# SCH_USB-HUB_2024-07-15.net
KiCad netlist of a schematic drawn in EasyEDA
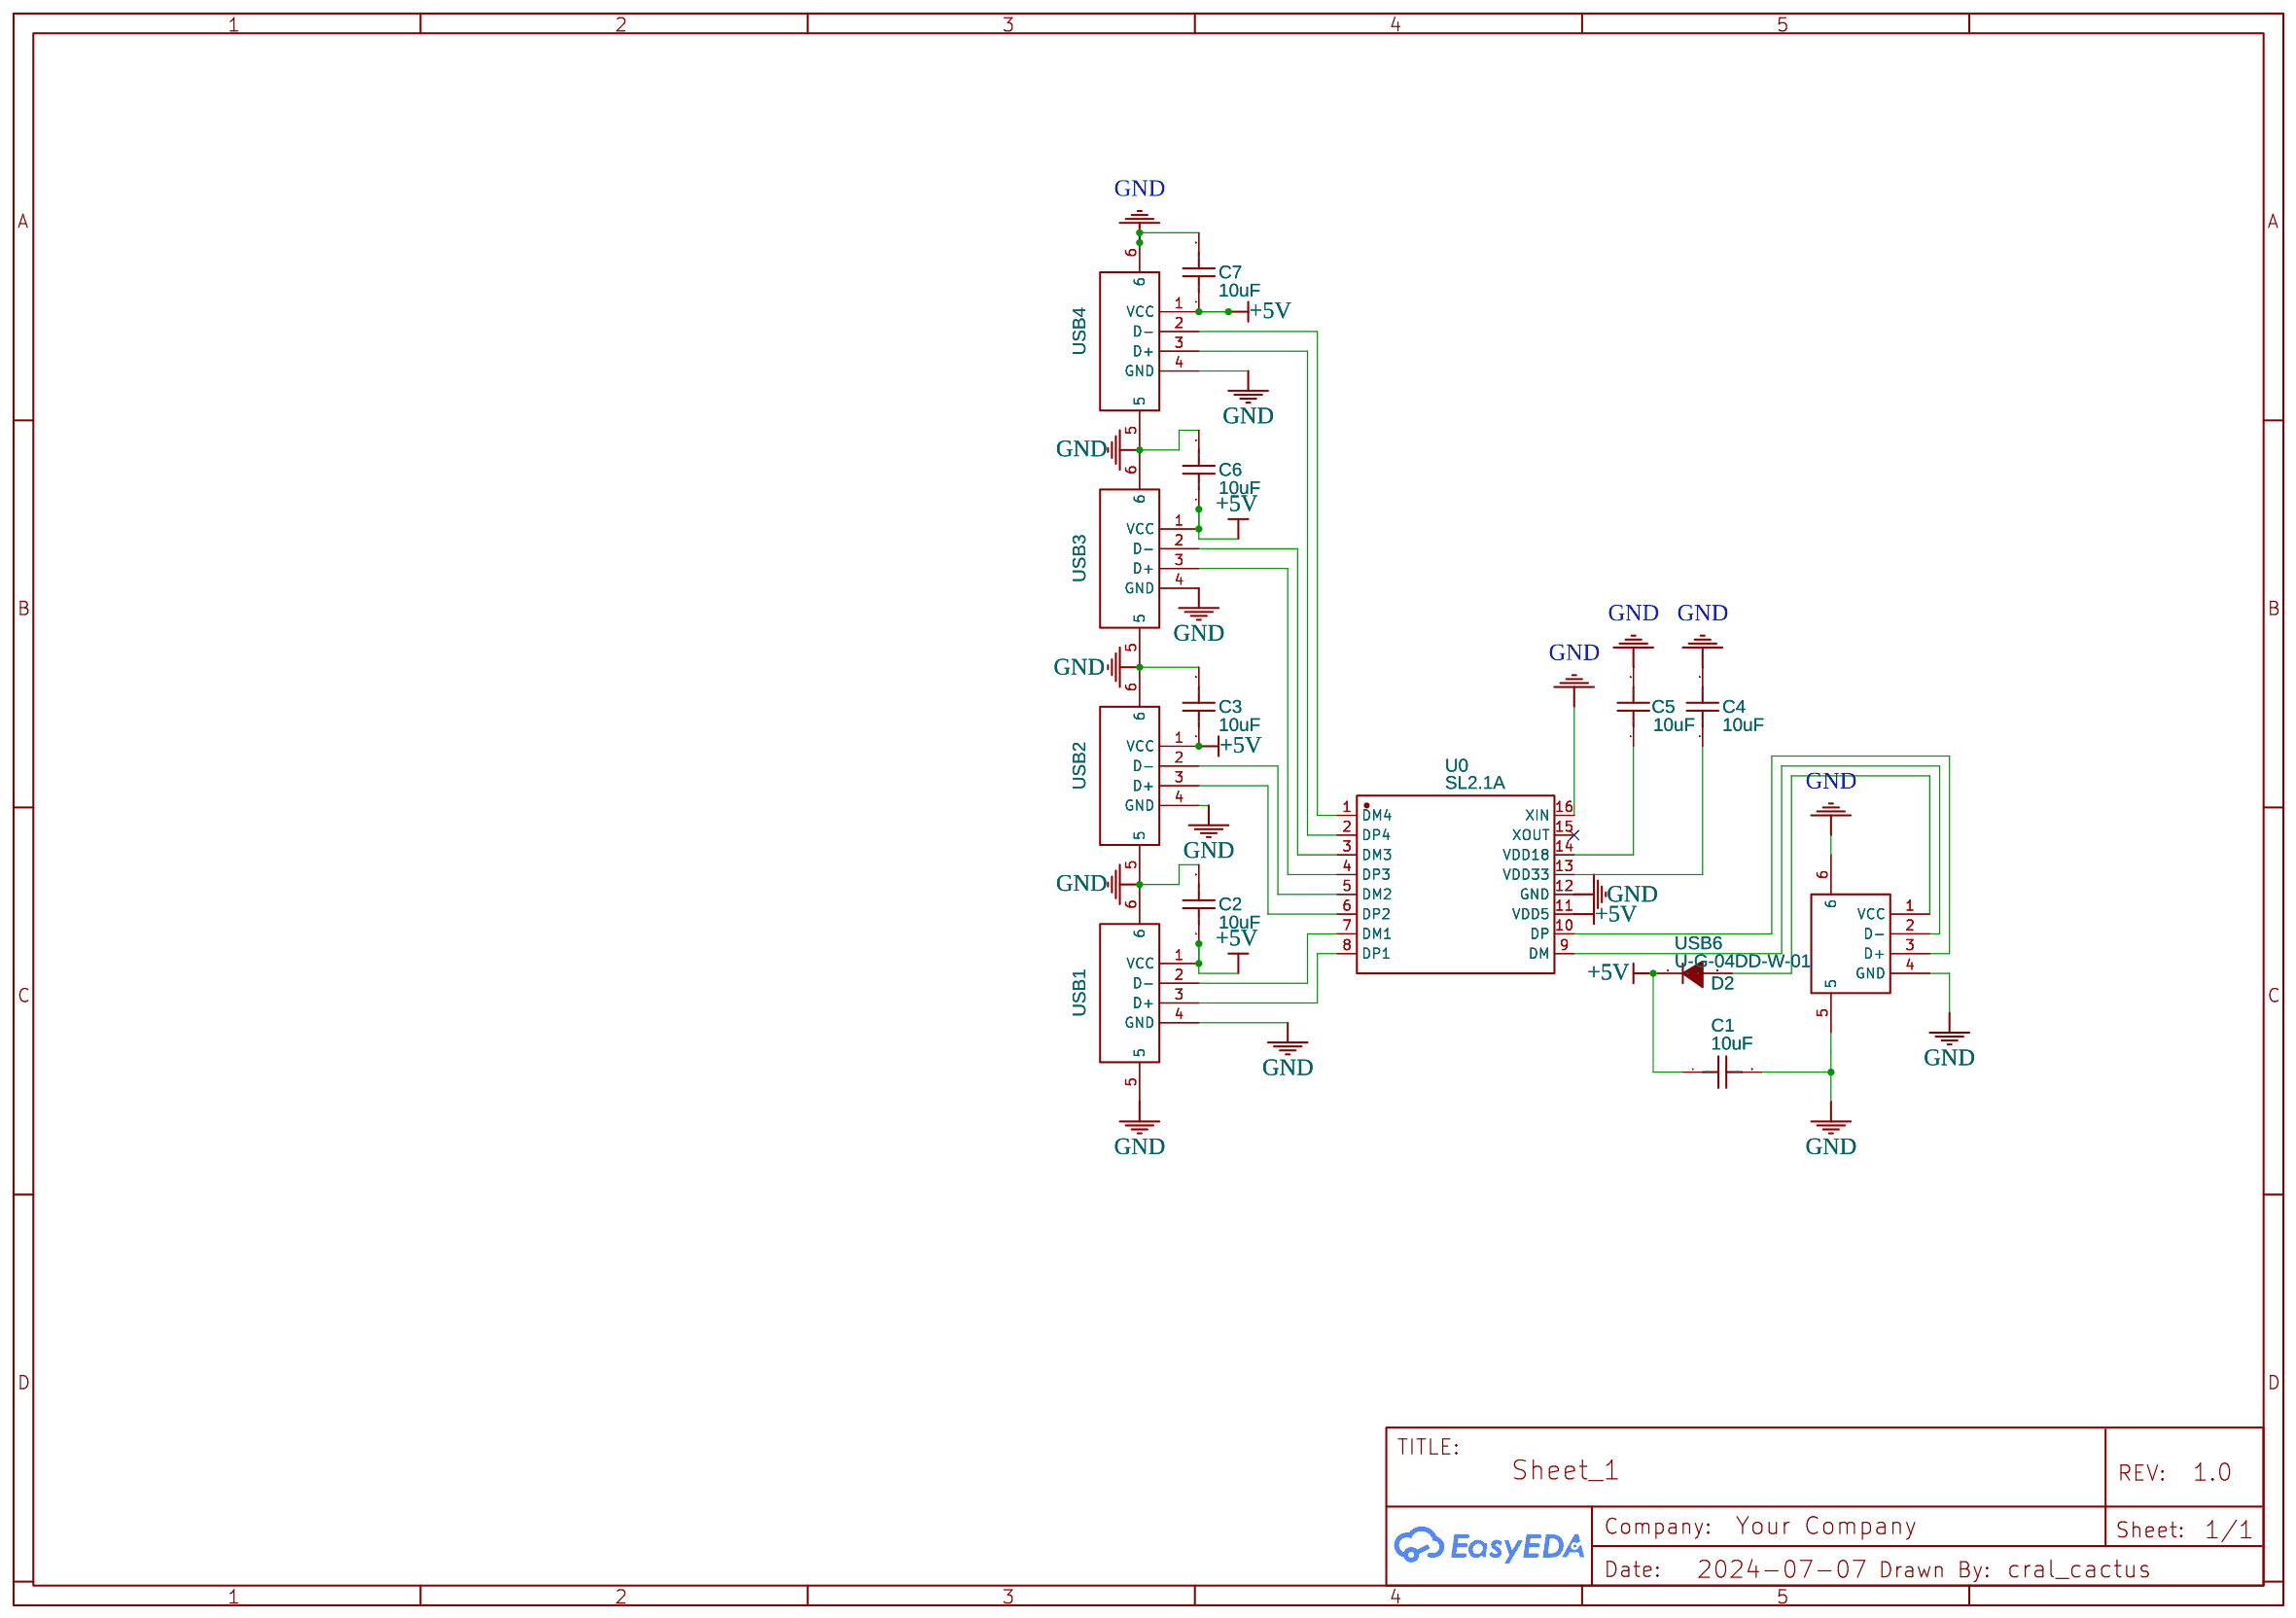
[diagram p0: schematic sheet]

(export (version "E")
  (design (tool "Eeschema 10.0.6"))
  (components
    (comp (ref "C1")
      (value "10uF")
      (fields
        (field (name "Manufacturer Part") "CL10A106KP8NNNC")
        (field (name "Manufacturer") "SAMSUNG(三星)")
      )
      (libsource (lib "") (part "CL10A106KP8NNNC_1"))
    )
    (comp (ref "C2")
      (value "10uF")
      (fields
        (field (name "Manufacturer Part") "CL10A106KP8NNNC")
        (field (name "Manufacturer") "SAMSUNG(三星)")
      )
      (libsource (lib "") (part "CL10A106KP8NNNC"))
    )
    (comp (ref "C3")
      (value "10uF")
      (fields
        (field (name "Manufacturer Part") "CL10A106KP8NNNC")
        (field (name "Manufacturer") "SAMSUNG(三星)")
      )
      (libsource (lib "") (part "CL10A106KP8NNNC"))
    )
    (comp (ref "C4")
      (value "10uF")
      (fields
        (field (name "Manufacturer Part") "CL10A106KP8NNNC")
        (field (name "Manufacturer") "SAMSUNG(三星)")
      )
      (libsource (lib "") (part "CL10A106KP8NNNC"))
    )
    (comp (ref "C5")
      (value "10uF")
      (fields
        (field (name "Manufacturer Part") "CL10A106KP8NNNC")
        (field (name "Manufacturer") "SAMSUNG(三星)")
      )
      (libsource (lib "") (part "CL10A106KP8NNNC"))
    )
    (comp (ref "C6")
      (value "10uF")
      (fields
        (field (name "Manufacturer Part") "CL10A106KP8NNNC")
        (field (name "Manufacturer") "SAMSUNG(三星)")
      )
      (libsource (lib "") (part "CL10A106KP8NNNC"))
    )
    (comp (ref "C7")
      (value "10uF")
      (fields
        (field (name "Manufacturer Part") "CL10A106KP8NNNC")
        (field (name "Manufacturer") "SAMSUNG(三星)")
      )
      (libsource (lib "") (part "CL10A106KP8NNNC"))
    )
    (comp (ref "D2")
      (value "NSR0320MW2T1G")
      (fields (field (name "Manufacturer") "onsemi(安森美)"))
      (libsource (lib "") (part "NSR0320MW2T1G"))
    )
    (comp (ref "U0")
      (value "SL2.1A")
      (fields (field (name "Manufacturer") "CoreChips(和芯润德)"))
      (libsource (lib "") (part "SL2.1A"))
    )
    (comp (ref "USB1")
      (value "USB-AF-90-14.4X13.6-H7.0-DIP")
      (fields (field (name "Manufacturer Part") "903-131A1011D10100") (field (name "Manufacturer") "精拓金"))
      (libsource (lib "") (part "USB-AF-90-14.4X13.6-H7.0-DIP"))
    )
    (comp (ref "USB2")
      (value "USB-AF-90-14.4X13.6-H7.0-DIP")
      (fields (field (name "Manufacturer Part") "903-131A1011D10100") (field (name "Manufacturer") "精拓金"))
      (libsource (lib "") (part "USB-AF-90-14.4X13.6-H7.0-DIP"))
    )
    (comp (ref "USB3")
      (value "USB-AF-90-14.4X13.6-H7.0-DIP")
      (fields (field (name "Manufacturer Part") "903-131A1011D10100") (field (name "Manufacturer") "精拓金"))
      (libsource (lib "") (part "USB-AF-90-14.4X13.6-H7.0-DIP"))
    )
    (comp (ref "USB4")
      (value "USB-AF-90-14.4X13.6-H7.0-DIP")
      (fields (field (name "Manufacturer Part") "903-131A1011D10100") (field (name "Manufacturer") "精拓金"))
      (libsource (lib "") (part "USB-AF-90-14.4X13.6-H7.0-DIP"))
    )
    (comp (ref "USB6")
      (value "U-G-04DD-W-01")
      (fields (field (name "Manufacturer Part") "U-G-O4DD-W-1") (field (name "Manufacturer") "韩国韩荣"))
      (libsource (lib "") (part "U-G-04DD-W-01"))
    )
  )
  (nets
    (net (code "1") (name "+5V") (class "Default")
      (node (ref "C1") (pin "1") (pinfunction "1_1") (pintype "unspecified"))
      (node (ref "C2") (pin "1") (pinfunction "1_1") (pintype "unspecified"))
      (node (ref "C3") (pin "1") (pinfunction "1_1") (pintype "unspecified"))
      (node (ref "C6") (pin "1") (pinfunction "1_1") (pintype "unspecified"))
      (node (ref "C7") (pin "1") (pinfunction "1_1") (pintype "unspecified"))
      (node (ref "D2") (pin "1") (pinfunction "C_1") (pintype "unspecified"))
      (node (ref "U0") (pin "11") (pinfunction "VDD5_11") (pintype "unspecified"))
      (node (ref "USB1") (pin "1") (pinfunction "VCC_1") (pintype "unspecified"))
      (node (ref "USB2") (pin "1") (pinfunction "VCC_1") (pintype "unspecified"))
      (node (ref "USB3") (pin "1") (pinfunction "VCC_1") (pintype "unspecified"))
      (node (ref "USB4") (pin "1") (pinfunction "VCC_1") (pintype "unspecified"))
    )
    (net (code "2") (name "GND") (class "Default")
      (node (ref "C1") (pin "2") (pinfunction "2_2") (pintype "unspecified"))
      (node (ref "C2") (pin "2") (pinfunction "2_2") (pintype "unspecified"))
      (node (ref "C3") (pin "2") (pinfunction "2_2") (pintype "unspecified"))
      (node (ref "C4") (pin "2") (pinfunction "2_2") (pintype "unspecified"))
      (node (ref "C5") (pin "2") (pinfunction "2_2") (pintype "unspecified"))
      (node (ref "C6") (pin "2") (pinfunction "2_2") (pintype "unspecified"))
      (node (ref "C7") (pin "2") (pinfunction "2_2") (pintype "unspecified"))
      (node (ref "U0") (pin "12") (pinfunction "GND_12") (pintype "unspecified"))
      (node (ref "U0") (pin "16") (pinfunction "XIN_16") (pintype "unspecified"))
      (node (ref "USB1") (pin "4") (pinfunction "GND_4") (pintype "unspecified"))
      (node (ref "USB1") (pin "5") (pinfunction "5_5") (pintype "unspecified"))
      (node (ref "USB1") (pin "6") (pinfunction "6_6") (pintype "unspecified"))
      (node (ref "USB2") (pin "4") (pinfunction "GND_4") (pintype "unspecified"))
      (node (ref "USB2") (pin "5") (pinfunction "5_5") (pintype "unspecified"))
      (node (ref "USB2") (pin "6") (pinfunction "6_6") (pintype "unspecified"))
      (node (ref "USB3") (pin "4") (pinfunction "GND_4") (pintype "unspecified"))
      (node (ref "USB3") (pin "5") (pinfunction "5_5") (pintype "unspecified"))
      (node (ref "USB3") (pin "6") (pinfunction "6_6") (pintype "unspecified"))
      (node (ref "USB4") (pin "4") (pinfunction "GND_4") (pintype "unspecified"))
      (node (ref "USB4") (pin "5") (pinfunction "5_5") (pintype "unspecified"))
      (node (ref "USB4") (pin "6") (pinfunction "6_6") (pintype "unspecified"))
      (node (ref "USB6") (pin "4") (pinfunction "GND_4") (pintype "unspecified"))
      (node (ref "USB6") (pin "5") (pinfunction "5_5") (pintype "unspecified"))
      (node (ref "USB6") (pin "6") (pinfunction "6_6") (pintype "unspecified"))
    )
    (net (code "3") (name "Net-(D2-A)") (class "Default")
      (node (ref "D2") (pin "2") (pinfunction "A_2") (pintype "unspecified"))
      (node (ref "USB6") (pin "1") (pinfunction "VCC_1") (pintype "unspecified"))
    )
    (net (code "4") (name "Net-(U0-DM)") (class "Default")
      (node (ref "U0") (pin "9") (pinfunction "DM_9") (pintype "unspecified"))
      (node (ref "USB6") (pin "2") (pinfunction "D-_2") (pintype "unspecified"))
    )
    (net (code "5") (name "Net-(U0-DM1)") (class "Default")
      (node (ref "U0") (pin "7") (pinfunction "DM1_7") (pintype "unspecified"))
      (node (ref "USB1") (pin "2") (pinfunction "D-_2") (pintype "unspecified"))
    )
    (net (code "6") (name "Net-(U0-DM2)") (class "Default")
      (node (ref "U0") (pin "5") (pinfunction "DM2_5") (pintype "unspecified"))
      (node (ref "USB2") (pin "2") (pinfunction "D-_2") (pintype "unspecified"))
    )
    (net (code "7") (name "Net-(U0-DM3)") (class "Default")
      (node (ref "U0") (pin "3") (pinfunction "DM3_3") (pintype "unspecified"))
      (node (ref "USB3") (pin "2") (pinfunction "D-_2") (pintype "unspecified"))
    )
    (net (code "8") (name "Net-(U0-DM4)") (class "Default")
      (node (ref "U0") (pin "1") (pinfunction "DM4_1") (pintype "unspecified"))
      (node (ref "USB4") (pin "2") (pinfunction "D-_2") (pintype "unspecified"))
    )
    (net (code "9") (name "Net-(U0-DP)") (class "Default")
      (node (ref "U0") (pin "10") (pinfunction "DP_10") (pintype "unspecified"))
      (node (ref "USB6") (pin "3") (pinfunction "D+_3") (pintype "unspecified"))
    )
    (net (code "10") (name "Net-(U0-DP1)") (class "Default")
      (node (ref "U0") (pin "8") (pinfunction "DP1_8") (pintype "unspecified"))
      (node (ref "USB1") (pin "3") (pinfunction "D+_3") (pintype "unspecified"))
    )
    (net (code "11") (name "Net-(U0-DP2)") (class "Default")
      (node (ref "U0") (pin "6") (pinfunction "DP2_6") (pintype "unspecified"))
      (node (ref "USB2") (pin "3") (pinfunction "D+_3") (pintype "unspecified"))
    )
    (net (code "12") (name "Net-(U0-DP3)") (class "Default")
      (node (ref "U0") (pin "4") (pinfunction "DP3_4") (pintype "unspecified"))
      (node (ref "USB3") (pin "3") (pinfunction "D+_3") (pintype "unspecified"))
    )
    (net (code "13") (name "Net-(U0-DP4)") (class "Default")
      (node (ref "U0") (pin "2") (pinfunction "DP4_2") (pintype "unspecified"))
      (node (ref "USB4") (pin "3") (pinfunction "D+_3") (pintype "unspecified"))
    )
    (net (code "14") (name "Net-(U0-VDD18)") (class "Default")
      (node (ref "C5") (pin "1") (pinfunction "1_1") (pintype "unspecified"))
      (node (ref "U0") (pin "14") (pinfunction "VDD18_14") (pintype "unspecified"))
    )
    (net (code "15") (name "Net-(U0-VDD33)") (class "Default")
      (node (ref "C4") (pin "1") (pinfunction "1_1") (pintype "unspecified"))
      (node (ref "U0") (pin "13") (pinfunction "VDD33_13") (pintype "unspecified"))
    )
    (net (code "16") (name "unconnected-(U0-XOUT-Pad15)") (class "Default")
      (node (ref "U0") (pin "15") (pinfunction "XOUT_15") (pintype "unspecified+no_connect"))
    )
  )
)
